# Botdozer.net
KiCad netlist of a schematic drawn in EAGLE
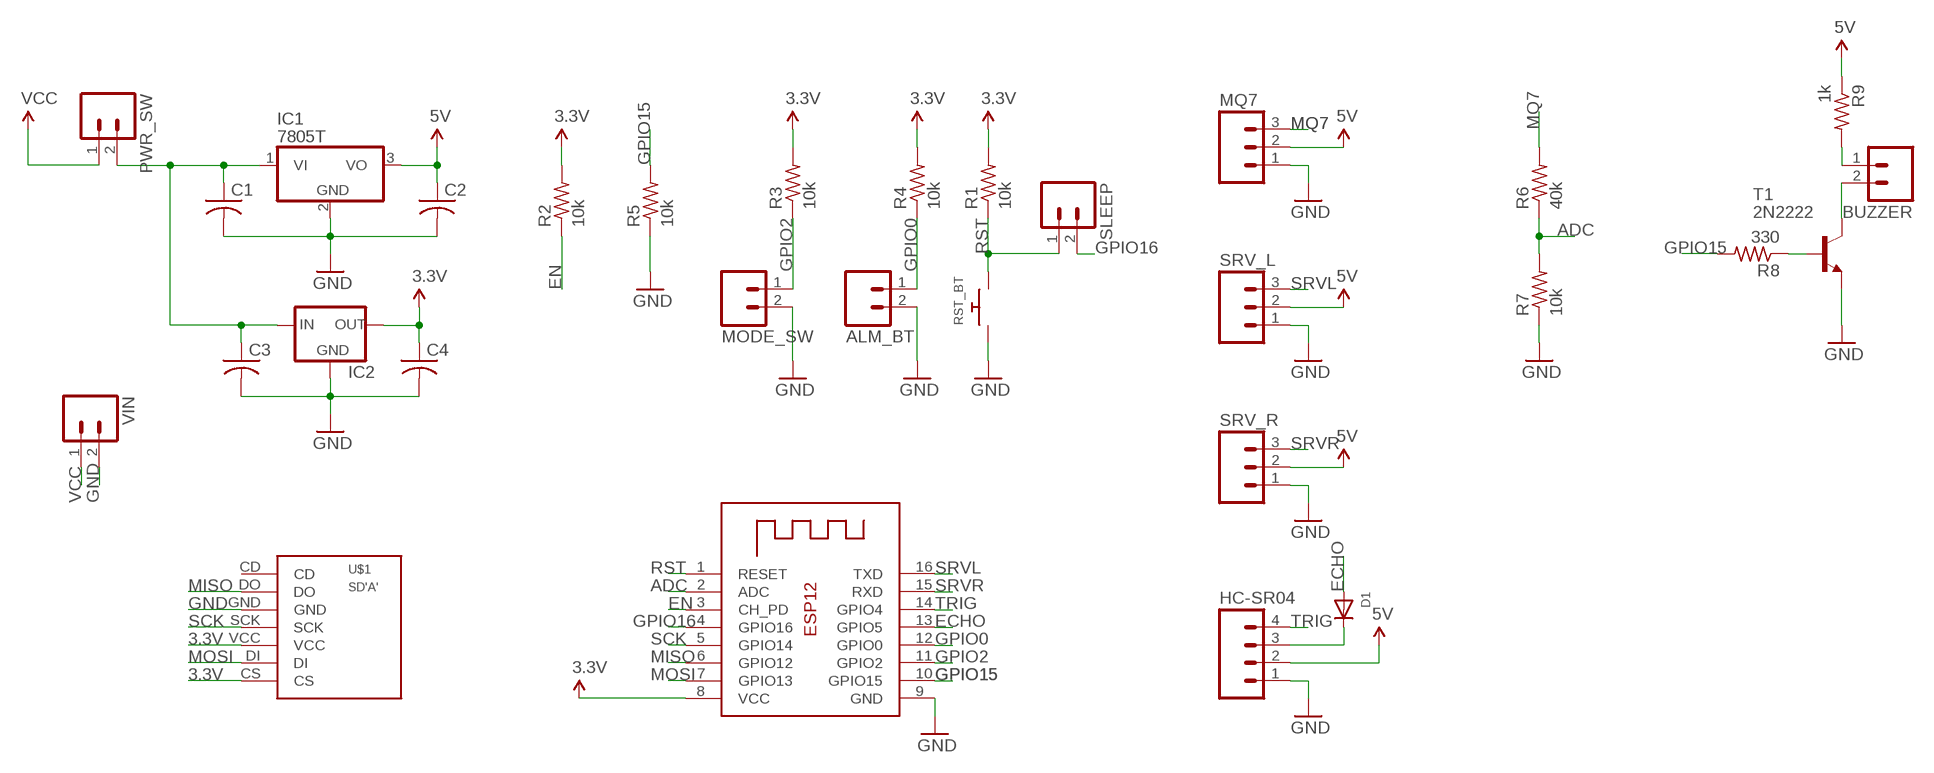
[diagram p0: schematic, sheet 1]

(export (version "E")
  (design (tool "Eeschema 10.0.6"))
  (components
    (comp (ref "ALM_BT")
      (value "M02PTH")
      (footprint "eagle-import:1X02")
      (libsource (lib "eagle-import") (part "M02PTH"))
    )
    (comp (ref "BUZZER")
      (value "M02PTH")
      (footprint "eagle-import:1X02")
      (libsource (lib "eagle-import") (part "M02PTH"))
    )
    (comp (ref "C1")
      (value "C-US025-025X050")
      (footprint "eagle-import:C025-025X050")
      (libsource (lib "eagle-import") (part "C-US025-025X050"))
    )
    (comp (ref "C2")
      (value "C-US025-025X050")
      (footprint "eagle-import:C025-025X050")
      (libsource (lib "eagle-import") (part "C-US025-025X050"))
    )
    (comp (ref "C3")
      (value "C-US025-025X050")
      (footprint "eagle-import:C025-025X050")
      (libsource (lib "eagle-import") (part "C-US025-025X050"))
    )
    (comp (ref "C4")
      (value "C-US025-025X050")
      (footprint "eagle-import:C025-025X050")
      (libsource (lib "eagle-import") (part "C-US025-025X050"))
    )
    (comp (ref "D1")
      (value "DIODEDO-1N4148")
      (footprint "eagle-import:DO-1N4148")
      (libsource (lib "eagle-import") (part "DIODEDO-1N4148"))
    )
    (comp (ref "HC-SR04")
      (value "M04PTH")
      (footprint "eagle-import:1X04")
      (libsource (lib "eagle-import") (part "M04PTH"))
    )
    (comp (ref "IC1")
      (value "7805T")
      (footprint "eagle-import:TO220H")
      (libsource (lib "eagle-import") (part "78T05"))
    )
    (comp (ref "IC2")
      (value "78XXL")
      (footprint "eagle-import:78XXL")
      (libsource (lib "eagle-import") (part "78XXL"))
    )
    (comp (ref "MODE_SW")
      (value "M02PTH")
      (footprint "eagle-import:1X02")
      (libsource (lib "eagle-import") (part "M02PTH"))
    )
    (comp (ref "MQ7")
      (value "M03PTH")
      (footprint "eagle-import:1X03")
      (libsource (lib "eagle-import") (part "M03PTH"))
    )
    (comp (ref "PWR_SW")
      (value "M02PTH")
      (footprint "eagle-import:1X02")
      (libsource (lib "eagle-import") (part "M02PTH"))
    )
    (comp (ref "R1")
      (value "10k")
      (footprint "eagle-import:0207_10")
      (libsource (lib "eagle-import") (part "R-US_0207/10"))
    )
    (comp (ref "R2")
      (value "10k")
      (footprint "eagle-import:0207_10")
      (libsource (lib "eagle-import") (part "R-US_0207/10"))
    )
    (comp (ref "R3")
      (value "10k")
      (footprint "eagle-import:0207_10")
      (libsource (lib "eagle-import") (part "R-US_0207/10"))
    )
    (comp (ref "R4")
      (value "10k")
      (footprint "eagle-import:0207_10")
      (libsource (lib "eagle-import") (part "R-US_0207/10"))
    )
    (comp (ref "R5")
      (value "10k")
      (footprint "eagle-import:0207_10")
      (libsource (lib "eagle-import") (part "R-US_0207/10"))
    )
    (comp (ref "R6")
      (value "40k")
      (footprint "eagle-import:0207_10")
      (libsource (lib "eagle-import") (part "R-US_0207/10"))
    )
    (comp (ref "R7")
      (value "10k")
      (footprint "eagle-import:0207_10")
      (libsource (lib "eagle-import") (part "R-US_0207/10"))
    )
    (comp (ref "R8")
      (value "330")
      (footprint "eagle-import:0207_10")
      (libsource (lib "eagle-import") (part "R-US_0207/10"))
    )
    (comp (ref "R9")
      (value "1k")
      (footprint "eagle-import:0207_10")
      (libsource (lib "eagle-import") (part "R-US_0207/10"))
    )
    (comp (ref "RST_BT")
      (value "SWITCH_PUSHBUTTONEVQ-PE")
      (footprint "eagle-import:TACT_PANA-EVQ")
      (libsource (lib "eagle-import") (part "SWITCH_PUSHBUTTONEVQ-PE"))
    )
    (comp (ref "SLEEP")
      (value "M02PTH")
      (footprint "eagle-import:1X02")
      (libsource (lib "eagle-import") (part "M02PTH"))
    )
    (comp (ref "SRV_L")
      (value "M03PTH")
      (footprint "eagle-import:1X03")
      (libsource (lib "eagle-import") (part "M03PTH"))
    )
    (comp (ref "SRV_R")
      (value "M03PTH")
      (footprint "eagle-import:1X03")
      (libsource (lib "eagle-import") (part "M03PTH"))
    )
    (comp (ref "T1")
      (value "2N2222")
      (footprint "eagle-import:TO92-EBC-OVAL")
      (libsource (lib "eagle-import") (part "2N2222"))
    )
    (comp (ref "U$1")
      (value "SD'A'")
      (footprint "eagle-import:SD_BR")
      (libsource (lib "eagle-import") (part "SD'A'"))
    )
    (comp (ref "VIN")
      (value "M02PTH")
      (footprint "eagle-import:1X02")
      (libsource (lib "eagle-import") (part "M02PTH"))
    )
    (comp (ref "X1")
      (value "ESP-12")
      (footprint "eagle-import:ESP-12")
      (libsource (lib "eagle-import") (part "ESP-12"))
    )
  )
  (nets
    (net (code "1") (name "/ADC") (class "Default")
      (node (ref "R6") (pin "1") (pinfunction "1_1") (pintype "passive"))
      (node (ref "R7") (pin "2") (pinfunction "2_2") (pintype "passive"))
      (node (ref "X1") (pin "2") (pinfunction "ADC_2") (pintype "passive"))
    )
    (net (code "2") (name "/ECHO") (class "Default")
      (node (ref "D1") (pin "A") (pinfunction "A_A") (pintype "passive"))
      (node (ref "X1") (pin "13") (pinfunction "GPIO5_13") (pintype "bidirectional"))
    )
    (net (code "3") (name "/EN") (class "Default")
      (node (ref "R2") (pin "1") (pinfunction "1_1") (pintype "passive"))
      (node (ref "X1") (pin "3") (pinfunction "CH_PD_3") (pintype "input"))
    )
    (net (code "4") (name "/GPIO0") (class "Default")
      (node (ref "ALM_BT") (pin "1") (pinfunction "1_1") (pintype "passive"))
      (node (ref "R4") (pin "1") (pinfunction "1_1") (pintype "passive"))
      (node (ref "X1") (pin "12") (pinfunction "GPIO0_12") (pintype "bidirectional"))
    )
    (net (code "5") (name "/GPIO2") (class "Default")
      (node (ref "MODE_SW") (pin "1") (pinfunction "1_1") (pintype "passive"))
      (node (ref "R3") (pin "1") (pinfunction "1_1") (pintype "passive"))
      (node (ref "X1") (pin "11") (pinfunction "GPIO2_11") (pintype "bidirectional"))
    )
    (net (code "6") (name "/GPIO15") (class "Default")
      (node (ref "R5") (pin "2") (pinfunction "2_2") (pintype "passive"))
      (node (ref "R8") (pin "2") (pinfunction "2_2") (pintype "passive"))
      (node (ref "X1") (pin "10") (pinfunction "GPIO15_10") (pintype "bidirectional"))
    )
    (net (code "7") (name "/GPIO16") (class "Default")
      (node (ref "SLEEP") (pin "2") (pinfunction "2_2") (pintype "passive"))
      (node (ref "X1") (pin "4") (pinfunction "GPIO16_4") (pintype "bidirectional"))
    )
    (net (code "8") (name "/MISO") (class "Default")
      (node (ref "U$1") (pin "DO") (pinfunction "DO_DO") (pintype "bidirectional"))
      (node (ref "X1") (pin "6") (pinfunction "GPIO12_6") (pintype "bidirectional"))
    )
    (net (code "9") (name "/MOSI") (class "Default")
      (node (ref "U$1") (pin "DI") (pinfunction "DI_DI") (pintype "bidirectional"))
      (node (ref "X1") (pin "7") (pinfunction "GPIO13_7") (pintype "bidirectional"))
    )
    (net (code "10") (name "/MQ7") (class "Default")
      (node (ref "MQ7") (pin "3") (pinfunction "3_3") (pintype "passive"))
      (node (ref "R6") (pin "2") (pinfunction "2_2") (pintype "passive"))
    )
    (net (code "11") (name "/RST") (class "Default")
      (node (ref "R1") (pin "1") (pinfunction "1_1") (pintype "passive"))
      (node (ref "RST_BT") (pin "P$2") (pinfunction "P$2_P$2") (pintype "passive"))
      (node (ref "SLEEP") (pin "1") (pinfunction "1_1") (pintype "passive"))
      (node (ref "X1") (pin "1") (pinfunction "RESET_1") (pintype "input"))
    )
    (net (code "12") (name "/SCK") (class "Default")
      (node (ref "U$1") (pin "SCK") (pinfunction "SCK_SCK") (pintype "bidirectional"))
      (node (ref "X1") (pin "5") (pinfunction "GPIO14_5") (pintype "bidirectional"))
    )
    (net (code "13") (name "/SRVL") (class "Default")
      (node (ref "SRV_L") (pin "3") (pinfunction "3_3") (pintype "passive"))
      (node (ref "X1") (pin "16") (pinfunction "TXD_16") (pintype "output"))
    )
    (net (code "14") (name "/SRVR") (class "Default")
      (node (ref "SRV_R") (pin "3") (pinfunction "3_3") (pintype "passive"))
      (node (ref "X1") (pin "15") (pinfunction "RXD_15") (pintype "input"))
    )
    (net (code "15") (name "/TRIG") (class "Default")
      (node (ref "HC-SR04") (pin "4") (pinfunction "4_4") (pintype "passive"))
      (node (ref "X1") (pin "14") (pinfunction "GPIO4_14") (pintype "bidirectional"))
    )
    (net (code "16") (name "3.3V") (class "Default")
      (node (ref "C4") (pin "1") (pinfunction "1_1") (pintype "passive"))
      (node (ref "IC2") (pin "OUT") (pinfunction "OUT_OUT") (pintype "passive"))
      (node (ref "R1") (pin "2") (pinfunction "2_2") (pintype "passive"))
      (node (ref "R2") (pin "2") (pinfunction "2_2") (pintype "passive"))
      (node (ref "R3") (pin "2") (pinfunction "2_2") (pintype "passive"))
      (node (ref "R4") (pin "2") (pinfunction "2_2") (pintype "passive"))
      (node (ref "U$1") (pin "CS") (pinfunction "CS_CS") (pintype "bidirectional"))
      (node (ref "U$1") (pin "VCC") (pinfunction "VCC_VCC") (pintype "bidirectional"))
      (node (ref "X1") (pin "8") (pinfunction "VCC_8") (pintype "power_in"))
    )
    (net (code "17") (name "5V") (class "Default")
      (node (ref "C2") (pin "1") (pinfunction "1_1") (pintype "passive"))
      (node (ref "HC-SR04") (pin "2") (pinfunction "2_2") (pintype "passive"))
      (node (ref "IC1") (pin "3") (pinfunction "VO_3") (pintype "passive"))
      (node (ref "MQ7") (pin "2") (pinfunction "2_2") (pintype "passive"))
      (node (ref "R9") (pin "1") (pinfunction "1_1") (pintype "passive"))
      (node (ref "SRV_L") (pin "2") (pinfunction "2_2") (pintype "passive"))
      (node (ref "SRV_R") (pin "2") (pinfunction "2_2") (pintype "passive"))
    )
    (net (code "18") (name "GND") (class "Default")
      (node (ref "ALM_BT") (pin "2") (pinfunction "2_2") (pintype "passive"))
      (node (ref "C1") (pin "2") (pinfunction "2_2") (pintype "passive"))
      (node (ref "C2") (pin "2") (pinfunction "2_2") (pintype "passive"))
      (node (ref "C3") (pin "2") (pinfunction "2_2") (pintype "passive"))
      (node (ref "C4") (pin "2") (pinfunction "2_2") (pintype "passive"))
      (node (ref "HC-SR04") (pin "1") (pinfunction "1_1") (pintype "passive"))
      (node (ref "IC1") (pin "2") (pinfunction "GND_2") (pintype "passive"))
      (node (ref "IC2") (pin "GND") (pinfunction "GND_GND") (pintype "input"))
      (node (ref "MODE_SW") (pin "2") (pinfunction "2_2") (pintype "passive"))
      (node (ref "MQ7") (pin "1") (pinfunction "1_1") (pintype "passive"))
      (node (ref "R5") (pin "1") (pinfunction "1_1") (pintype "passive"))
      (node (ref "R7") (pin "1") (pinfunction "1_1") (pintype "passive"))
      (node (ref "RST_BT") (pin "P$1") (pinfunction "P$1_P$1") (pintype "passive"))
      (node (ref "SRV_L") (pin "1") (pinfunction "1_1") (pintype "passive"))
      (node (ref "SRV_R") (pin "1") (pinfunction "1_1") (pintype "passive"))
      (node (ref "T1") (pin "E") (pinfunction "E_E") (pintype "passive"))
      (node (ref "U$1") (pin "GND") (pinfunction "GND_GND") (pintype "bidirectional"))
      (node (ref "VIN") (pin "2") (pinfunction "2_2") (pintype "passive"))
      (node (ref "X1") (pin "9") (pinfunction "GND_9") (pintype "power_in"))
    )
    (net (code "19") (name "Net-(BUZZER-Pad1)") (class "Default")
      (node (ref "BUZZER") (pin "1") (pinfunction "1_1") (pintype "passive"))
      (node (ref "R9") (pin "2") (pinfunction "2_2") (pintype "passive"))
    )
    (net (code "20") (name "Net-(BUZZER-Pad2)") (class "Default")
      (node (ref "BUZZER") (pin "2") (pinfunction "2_2") (pintype "passive"))
      (node (ref "T1") (pin "C") (pinfunction "C_C") (pintype "passive"))
    )
    (net (code "21") (name "Net-(D1-PadC)") (class "Default")
      (node (ref "D1") (pin "C") (pinfunction "C_C") (pintype "passive"))
      (node (ref "HC-SR04") (pin "3") (pinfunction "3_3") (pintype "passive"))
    )
    (net (code "22") (name "Net-(IC1-VI)") (class "Default")
      (node (ref "C1") (pin "1") (pinfunction "1_1") (pintype "passive"))
      (node (ref "C3") (pin "1") (pinfunction "1_1") (pintype "passive"))
      (node (ref "IC1") (pin "1") (pinfunction "VI_1") (pintype "input"))
      (node (ref "IC2") (pin "IN") (pinfunction "IN_IN") (pintype "input"))
      (node (ref "PWR_SW") (pin "2") (pinfunction "2_2") (pintype "passive"))
    )
    (net (code "23") (name "Net-(R8-Pad1)") (class "Default")
      (node (ref "R8") (pin "1") (pinfunction "1_1") (pintype "passive"))
      (node (ref "T1") (pin "B") (pinfunction "B_B") (pintype "passive"))
    )
    (net (code "24") (name "VCC") (class "Default")
      (node (ref "PWR_SW") (pin "1") (pinfunction "1_1") (pintype "passive"))
      (node (ref "VIN") (pin "1") (pinfunction "1_1") (pintype "passive"))
    )
    (net (code "25") (name "unconnected-(U$1-PadCD)") (class "Default")
      (node (ref "U$1") (pin "CD") (pinfunction "CD_CD") (pintype "bidirectional"))
    )
  )
)
